# boxer_I2C_diff.net
KiCad netlist of a schematic drawn in Altium Designer
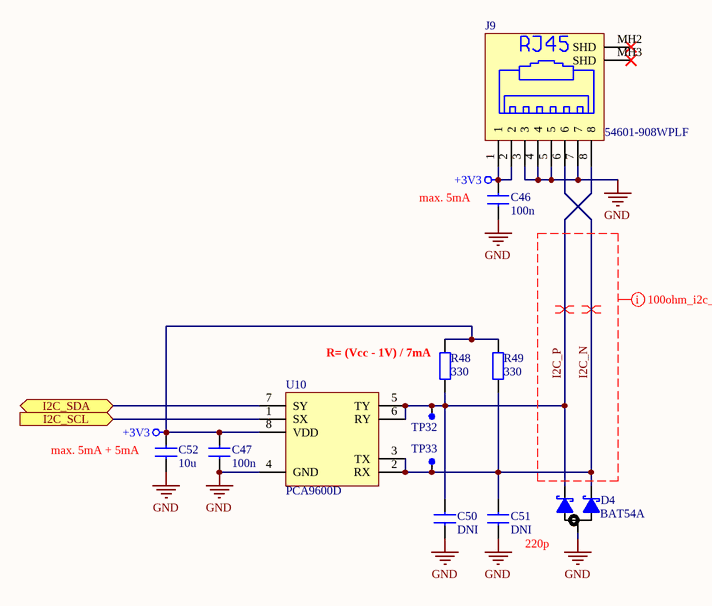
[diagram p0: boxer_I2C_diff.SchDoc]

(export (version "E")
  (design (tool "Eeschema 10.0.6"))
  (components
    (comp (ref "C46")
      (value "100n")
      (footprint "C_0805")
      (description "Capacitor")
      (libsource (lib "boxer_pas") (part "Capacitor"))
    )
    (comp (ref "C47")
      (value "100n")
      (footprint "C_0805")
      (description "Capacitor")
      (libsource (lib "boxer_pas") (part "Capacitor"))
    )
    (comp (ref "C50")
      (value "DNI")
      (footprint "C_0805")
      (description "Capacitor")
      (libsource (lib "boxer_pas") (part "Capacitor"))
    )
    (comp (ref "C51")
      (value "DNI")
      (footprint "C_0805")
      (description "Capacitor")
      (libsource (lib "boxer_pas") (part "Capacitor"))
    )
    (comp (ref "C52")
      (value "10u")
      (footprint "C_1206")
      (description "Capacitor")
      (libsource (lib "boxer_pas") (part "Capacitor"))
    )
    (comp (ref "D4")
      (value "BAT54A")
      (footprint "SOT-23")
      (description "dual Schottky diode common anode")
      (libsource (lib "boxer_pas") (part "Diode Schottky3"))
    )
    (comp (ref "J9")
      (value "54601-908WPLF")
      (footprint "RJ45_54601-908WPLF")
      (description "RJ45 Socket, 8pin, No Key, Molex MX-95001-2881")
      (libsource (lib "boxer_mechanical") (part "RJ45-8"))
    )
    (comp (ref "R48")
      (value "330")
      (footprint "R_0805")
      (description "Resistor")
      (libsource (lib "boxer_pas") (part "Resistor"))
    )
    (comp (ref "R49")
      (value "330")
      (footprint "R_0805")
      (description "Resistor")
      (libsource (lib "boxer_pas") (part "Resistor"))
    )
    (comp (ref "TP32")
      (value "TEST PAD")
      (footprint "PIN")
      (libsource (lib "boxer_mechanical") (part "TEST_PAD"))
    )
    (comp (ref "TP33")
      (value "TEST PAD")
      (footprint "PIN")
      (libsource (lib "boxer_mechanical") (part "TEST_PAD"))
    )
    (comp (ref "U10")
      (value "PCA9600D")
      (footprint "SO8")
      (description "Dual bidirectional I2C bus buffer")
      (libsource (lib "boxer_ic") (part "PCA9600"))
    )
  )
  (nets
    (net (code "1") (name "+3V3") (class "Default")
      (node (ref "C46") (pin "2") (pinfunction "2_2") (pintype "passive"))
      (node (ref "C47") (pin "2") (pinfunction "2_2") (pintype "passive"))
      (node (ref "C52") (pin "2") (pinfunction "2_2") (pintype "passive"))
      (node (ref "J9") (pin "1") (pinfunction "1_1") (pintype "passive"))
      (node (ref "J9") (pin "2") (pinfunction "2_2") (pintype "passive"))
      (node (ref "R48") (pin "2") (pinfunction "2_2") (pintype "passive"))
      (node (ref "R49") (pin "2") (pinfunction "2_2") (pintype "passive"))
      (node (ref "U10") (pin "8") (pinfunction "VDD_8") (pintype "passive"))
    )
    (net (code "2") (name "/I2C_N") (class "Default")
      (node (ref "C51") (pin "2") (pinfunction "2_2") (pintype "passive"))
      (node (ref "D4") (pin "1") (pinfunction "A_1") (pintype "passive"))
      (node (ref "J9") (pin "6") (pinfunction "6_6") (pintype "passive"))
      (node (ref "R49") (pin "1") (pinfunction "1_1") (pintype "passive"))
      (node (ref "TP33") (pin "1") (pinfunction "1_1") (pintype "passive"))
      (node (ref "U10") (pin "2") (pinfunction "RX_2") (pintype "passive"))
      (node (ref "U10") (pin "3") (pinfunction "TX_3") (pintype "passive"))
    )
    (net (code "3") (name "/I2C_P") (class "Default")
      (node (ref "C50") (pin "2") (pinfunction "2_2") (pintype "passive"))
      (node (ref "D4") (pin "2") (pinfunction "A_2") (pintype "passive"))
      (node (ref "J9") (pin "8") (pinfunction "8_8") (pintype "passive"))
      (node (ref "R48") (pin "1") (pinfunction "1_1") (pintype "passive"))
      (node (ref "TP32") (pin "1") (pinfunction "1_1") (pintype "passive"))
      (node (ref "U10") (pin "5") (pinfunction "TY_5") (pintype "passive"))
      (node (ref "U10") (pin "6") (pinfunction "RY_6") (pintype "passive"))
    )
    (net (code "4") (name "/I2C_SCL") (class "Default")
      (node (ref "U10") (pin "1") (pinfunction "SX_1") (pintype "passive"))
    )
    (net (code "5") (name "/I2C_SDA") (class "Default")
      (node (ref "U10") (pin "7") (pinfunction "SY_7") (pintype "passive"))
    )
    (net (code "6") (name "GND") (class "Default")
      (node (ref "C46") (pin "1") (pinfunction "1_1") (pintype "passive"))
      (node (ref "C47") (pin "1") (pinfunction "1_1") (pintype "passive"))
      (node (ref "C50") (pin "1") (pinfunction "1_1") (pintype "passive"))
      (node (ref "C51") (pin "1") (pinfunction "1_1") (pintype "passive"))
      (node (ref "C52") (pin "1") (pinfunction "1_1") (pintype "passive"))
      (node (ref "D4") (pin "3") (pinfunction "K_3") (pintype "passive"))
      (node (ref "J9") (pin "3") (pinfunction "3_3") (pintype "passive"))
      (node (ref "J9") (pin "4") (pinfunction "4_4") (pintype "passive"))
      (node (ref "J9") (pin "5") (pinfunction "5_5") (pintype "passive"))
      (node (ref "J9") (pin "7") (pinfunction "7_7") (pintype "passive"))
      (node (ref "U10") (pin "4") (pinfunction "GND_4") (pintype "passive"))
    )
    (net (code "7") (name "unconnected-(J9-SHD-PadMH2)") (class "Default")
      (node (ref "J9") (pin "MH2") (pinfunction "SHD_MH2") (pintype "passive+no_connect"))
    )
    (net (code "8") (name "unconnected-(J9-SHD-PadMH3)") (class "Default")
      (node (ref "J9") (pin "MH3") (pinfunction "SHD_MH3") (pintype "passive+no_connect"))
    )
  )
)
